# DRV8316.net
KiCad netlist of a schematic drawn in Altium Designer
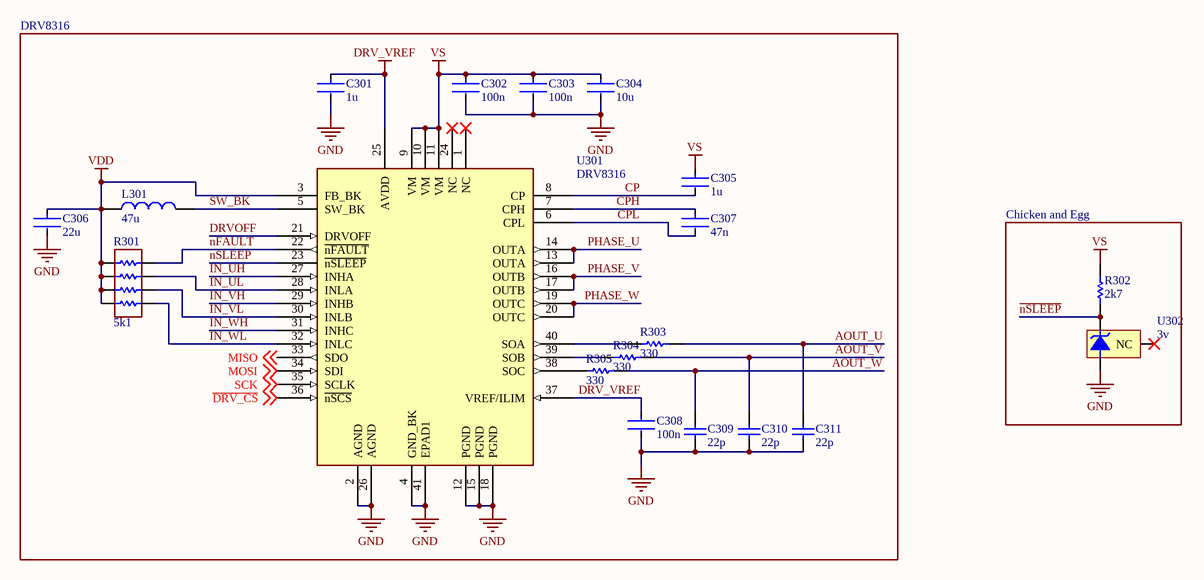
[diagram p0: DRV8316.SchDoc]

(export (version "E")
  (design (tool "Eeschema 10.0.6"))
  (components
    (comp (ref "C301")
      (value "1u")
      (footprint "FP-GRM155-0_1-MFG")
      (description "Chip Multilayer Ceramic Capacitors for General Purpose, 0402, 1.0uF, X5R, 15%, 20%, 50V")
      (libsource (lib "Main") (part "GRM155R61H105ME05D"))
    )
    (comp (ref "C302")
      (value "100n")
      (footprint "FP-GCM155-0_05-MFG")
      (description "Ceramic Capacitor for Automotive 100nF ±10% 50VDC X7R 0402 Paper T/R")
      (fields (field (name "TOLERANCE") "10%"))
      (libsource (lib "Main") (part "GCM155R71H104KE02J"))
    )
    (comp (ref "C303")
      (value "100n")
      (footprint "FP-GCM155-0_05-MFG")
      (description "Ceramic Capacitor for Automotive 100nF ±10% 50VDC X7R 0402 Paper T/R")
      (fields (field (name "TOLERANCE") "10%"))
      (libsource (lib "Main") (part "GCM155R71H104KE02J"))
    )
    (comp (ref "C304")
      (value "10u")
      (footprint "FP-GRT31C-0_2-IPC_C")
      (description "CAP CER 10UF 50V X5R 1206")
      (fields (field (name "TOLERANCE") "20%"))
      (libsource (lib "Main") (part "GRT31CR61H106ME01L"))
    )
    (comp (ref "C305")
      (value "1u")
      (footprint "FP-GRM155-0_1-MFG")
      (description "Chip Multilayer Ceramic Capacitors for General Purpose, 0402, 1.0uF, X5R, 15%, 20%, 50V")
      (libsource (lib "Main") (part "GRM155R61H105ME05D"))
    )
    (comp (ref "C306")
      (value "22u")
      (footprint "FP-GRM188-0_2-IPC_C")
      (description "Chip Multilayer Ceramic Capacitors for General Purpose, 0603, 22uF, X5R, 15%, 20%, 6.3V")
      (fields (field (name "TOLERANCE") "20%"))
      (libsource (lib "Main") (part "GRM188R60J226MEA0J"))
    )
    (comp (ref "C307")
      (value "47n")
      (footprint "FP-GRM155-0_05-MFG")
      (description "Chip Multilayer Ceramic Capacitors for General Purpose, 0402, 47000pF, X7R, 15%, 10%, 50V")
      (fields (field (name "TOLERANCE") "10%"))
      (libsource (lib "Main") (part "GRM155R71H473KE14D"))
    )
    (comp (ref "C308")
      (value "100n")
      (footprint "FP-GCM155-0_05-MFG")
      (description "Ceramic Capacitor for Automotive 100nF ±10% 50VDC X7R 0402 Paper T/R")
      (fields (field (name "TOLERANCE") "10%"))
      (libsource (lib "Main") (part "GCM155R71H104KE02J"))
    )
    (comp (ref "C309")
      (value "22p")
      (footprint "CAPC1005X55X25LL05T10")
      (fields (field (name "MANUFACTURER") "Murata") (field (name "PART NUMBER") "GRM1555C1H220GA01D"))
      (libsource (lib "Main") (part "GRM1555C1H220GA01D"))
    )
    (comp (ref "C310")
      (value "22p")
      (footprint "CAPC1005X55X25LL05T10")
      (fields (field (name "MANUFACTURER") "Murata") (field (name "PART NUMBER") "GRM1555C1H220GA01D"))
      (libsource (lib "Main") (part "GRM1555C1H220GA01D"))
    )
    (comp (ref "C311")
      (value "22p")
      (footprint "CAPC1005X55X25LL05T10")
      (fields (field (name "MANUFACTURER") "Murata") (field (name "PART NUMBER") "GRM1555C1H220GA01D"))
      (libsource (lib "Main") (part "GRM1555C1H220GA01D"))
    )
    (comp (ref "L301")
      (value "47u")
      (footprint "INDC3225X25N")
      (libsource (lib "Main") (part "L1210R470KDWIT"))
    )
    (comp (ref "R301")
      (value "5k1")
      (footprint "CAC-50P200X100-8L")
      (libsource (lib "Main") (part "EXB-28V512JX"))
    )
    (comp (ref "R302")
      (value "2k7")
      (footprint "RESC1005X04N")
      (fields (field (name "MANUFACTURER") "Panasonic") (field (name "PART NUMBER") "ERJ-2GEJ331X"))
      (libsource (lib "Main") (part "ERJ-2GEJ272X"))
    )
    (comp (ref "R303")
      (value "330")
      (footprint "RESC1005X04N")
      (fields (field (name "MANUFACTURER") "Panasonic") (field (name "PART NUMBER") "ERJ-2GEJ331X"))
      (libsource (lib "Main") (part "ERJ-2GEJ331X"))
    )
    (comp (ref "R304")
      (value "330")
      (footprint "RESC1005X04N")
      (fields (field (name "MANUFACTURER") "Panasonic") (field (name "PART NUMBER") "ERJ-2GEJ331X"))
      (libsource (lib "Main") (part "ERJ-2GEJ331X"))
    )
    (comp (ref "R305")
      (value "330")
      (footprint "RESC1005X04N")
      (fields (field (name "MANUFACTURER") "Panasonic") (field (name "PART NUMBER") "ERJ-2GEJ331X"))
      (libsource (lib "Main") (part "ERJ-2GEJ331X"))
    )
    (comp (ref "U301")
      (value "DRV8316")
      (footprint "QFN50P500X700X100_HS-41L")
      (libsource (lib "Main") (part "DRV8316"))
    )
    (comp (ref "U302")
      (value "3v")
      (footprint "SOT95P237X112-3L")
      (description "Precision Micropower Shunt Voltage Reference, 3-pin SOT-23, Pb-Free")
      (fields (field (name "MANUFACTURER") "National Semiconductor"))
      (libsource (lib "Main") (part "LM4040CIM3-3.0/NOPB"))
    )
  )
  (nets
    (net (code "1") (name "/AOUT_U") (class "Default")
      (node (ref "C311") (pin "2") (pinfunction "2_2") (pintype "passive"))
      (node (ref "R303") (pin "2") (pinfunction "2_2") (pintype "passive"))
    )
    (net (code "2") (name "/AOUT_V") (class "Default")
      (node (ref "C310") (pin "2") (pinfunction "2_2") (pintype "passive"))
      (node (ref "R304") (pin "2") (pinfunction "2_2") (pintype "passive"))
    )
    (net (code "3") (name "/AOUT_W") (class "Default")
      (node (ref "C309") (pin "2") (pinfunction "2_2") (pintype "passive"))
      (node (ref "R305") (pin "2") (pinfunction "2_2") (pintype "passive"))
    )
    (net (code "4") (name "/CP") (class "Default")
      (node (ref "C305") (pin "2") (pinfunction "2_2") (pintype "passive"))
      (node (ref "U301") (pin "8") (pinfunction "CP_8") (pintype "power_in"))
    )
    (net (code "5") (name "/CPH") (class "Default")
      (node (ref "C307") (pin "1") (pinfunction "1_1") (pintype "passive"))
      (node (ref "U301") (pin "7") (pinfunction "CPH_7") (pintype "power_in"))
    )
    (net (code "6") (name "/CPL") (class "Default")
      (node (ref "C307") (pin "2") (pinfunction "2_2") (pintype "passive"))
      (node (ref "U301") (pin "6") (pinfunction "CPL_6") (pintype "power_in"))
    )
    (net (code "7") (name "/DRVOFF") (class "Default")
      (node (ref "U301") (pin "21") (pinfunction "DRVOFF_21") (pintype "input"))
    )
    (net (code "8") (name "/IN_UH") (class "Default")
      (node (ref "U301") (pin "27") (pinfunction "INHA_27") (pintype "input"))
    )
    (net (code "9") (name "/IN_UL") (class "Default")
      (node (ref "R301") (pin "7") (pinfunction "7_7") (pintype "passive"))
      (node (ref "U301") (pin "28") (pinfunction "INLA_28") (pintype "input"))
    )
    (net (code "10") (name "/IN_VH") (class "Default")
      (node (ref "U301") (pin "29") (pinfunction "INHB_29") (pintype "input"))
    )
    (net (code "11") (name "/IN_VL") (class "Default")
      (node (ref "R301") (pin "6") (pinfunction "6_6") (pintype "passive"))
      (node (ref "U301") (pin "30") (pinfunction "INLB_30") (pintype "input"))
    )
    (net (code "12") (name "/IN_WH") (class "Default")
      (node (ref "U301") (pin "31") (pinfunction "INHC_31") (pintype "input"))
    )
    (net (code "13") (name "/IN_WL") (class "Default")
      (node (ref "R301") (pin "5") (pinfunction "5_5") (pintype "passive"))
      (node (ref "U301") (pin "32") (pinfunction "INLC_32") (pintype "input"))
    )
    (net (code "14") (name "/PHASE_U") (class "Default")
      (node (ref "U301") (pin "13") (pinfunction "OUTA_13") (pintype "output"))
      (node (ref "U301") (pin "14") (pinfunction "OUTA_14") (pintype "output"))
    )
    (net (code "15") (name "/PHASE_V") (class "Default")
      (node (ref "U301") (pin "16") (pinfunction "OUTB_16") (pintype "output"))
      (node (ref "U301") (pin "17") (pinfunction "OUTB_17") (pintype "output"))
    )
    (net (code "16") (name "/PHASE_W") (class "Default")
      (node (ref "U301") (pin "19") (pinfunction "OUTC_19") (pintype "output"))
      (node (ref "U301") (pin "20") (pinfunction "OUTC_20") (pintype "output"))
    )
    (net (code "17") (name "/SW_BK") (class "Default")
      (node (ref "L301") (pin "2") (pintype "passive"))
      (node (ref "U301") (pin "5") (pinfunction "SW_BK_5") (pintype "passive"))
    )
    (net (code "18") (name "/nFAULT") (class "Default")
      (node (ref "R301") (pin "8") (pinfunction "8_8") (pintype "passive"))
      (node (ref "U301") (pin "22") (pinfunction "nFAULT_22") (pintype "output"))
    )
    (net (code "19") (name "/nSLEEP") (class "Default")
      (node (ref "R302") (pin "1") (pinfunction "1_1") (pintype "passive"))
      (node (ref "U301") (pin "23") (pinfunction "nSLEEP_23") (pintype "passive"))
      (node (ref "U302") (pin "1") (pinfunction "+V_1") (pintype "passive"))
    )
    (net (code "20") (name "DRV_CS") (class "Default")
      (node (ref "U301") (pin "36") (pinfunction "nSCS_36") (pintype "input"))
    )
    (net (code "21") (name "DRV_VREF") (class "Default")
      (node (ref "C301") (pin "1") (pinfunction "1_1") (pintype "passive"))
      (node (ref "C308") (pin "1") (pinfunction "1_1") (pintype "passive"))
      (node (ref "U301") (pin "25") (pinfunction "AVDD_25") (pintype "power_in"))
      (node (ref "U301") (pin "37") (pinfunction "VREF/ILIM_37") (pintype "input"))
    )
    (net (code "22") (name "GND") (class "Default")
      (node (ref "C301") (pin "2") (pinfunction "2_2") (pintype "passive"))
      (node (ref "C302") (pin "2") (pinfunction "2_2") (pintype "passive"))
      (node (ref "C303") (pin "2") (pinfunction "2_2") (pintype "passive"))
      (node (ref "C304") (pin "2") (pinfunction "2_2") (pintype "passive"))
      (node (ref "C306") (pin "2") (pinfunction "2_2") (pintype "passive"))
      (node (ref "C308") (pin "2") (pinfunction "2_2") (pintype "passive"))
      (node (ref "C309") (pin "1") (pinfunction "1_1") (pintype "passive"))
      (node (ref "C310") (pin "1") (pinfunction "1_1") (pintype "passive"))
      (node (ref "C311") (pin "1") (pinfunction "1_1") (pintype "passive"))
      (node (ref "U301") (pin "12") (pinfunction "PGND_12") (pintype "power_in"))
      (node (ref "U301") (pin "15") (pinfunction "PGND_15") (pintype "power_in"))
      (node (ref "U301") (pin "18") (pinfunction "PGND_18") (pintype "power_in"))
      (node (ref "U301") (pin "2") (pinfunction "AGND_2") (pintype "power_in"))
      (node (ref "U301") (pin "26") (pinfunction "AGND_26") (pintype "power_in"))
      (node (ref "U301") (pin "4") (pinfunction "GND_BK_4") (pintype "power_in"))
      (node (ref "U301") (pin "41") (pinfunction "EPAD1_41") (pintype "power_in"))
      (node (ref "U302") (pin "2") (pinfunction "-V_2") (pintype "passive"))
    )
    (net (code "23") (name "MISO") (class "Default")
      (node (ref "U301") (pin "33") (pinfunction "SDO_33") (pintype "output"))
    )
    (net (code "24") (name "MOSI") (class "Default")
      (node (ref "U301") (pin "34") (pinfunction "SDI_34") (pintype "input"))
    )
    (net (code "25") (name "Net-(U301-SOA)") (class "Default")
      (node (ref "R303") (pin "1") (pinfunction "1_1") (pintype "passive"))
      (node (ref "U301") (pin "40") (pinfunction "SOA_40") (pintype "output"))
    )
    (net (code "26") (name "Net-(U301-SOB)") (class "Default")
      (node (ref "R304") (pin "1") (pinfunction "1_1") (pintype "passive"))
      (node (ref "U301") (pin "39") (pinfunction "SOB_39") (pintype "output"))
    )
    (net (code "27") (name "Net-(U301-SOC)") (class "Default")
      (node (ref "R305") (pin "1") (pinfunction "1_1") (pintype "passive"))
      (node (ref "U301") (pin "38") (pinfunction "SOC_38") (pintype "output"))
    )
    (net (code "28") (name "SCK") (class "Default")
      (node (ref "U301") (pin "35") (pinfunction "SCLK_35") (pintype "input"))
    )
    (net (code "29") (name "VDD") (class "Default")
      (node (ref "C306") (pin "1") (pinfunction "1_1") (pintype "passive"))
      (node (ref "L301") (pin "1") (pintype "passive"))
      (node (ref "R301") (pin "1") (pinfunction "1_1") (pintype "passive"))
      (node (ref "R301") (pin "2") (pinfunction "2_2") (pintype "passive"))
      (node (ref "R301") (pin "3") (pinfunction "3_3") (pintype "passive"))
      (node (ref "R301") (pin "4") (pinfunction "4_4") (pintype "passive"))
      (node (ref "U301") (pin "3") (pinfunction "FB_BK_3") (pintype "power_in"))
    )
    (net (code "30") (name "VS") (class "Default")
      (node (ref "C302") (pin "1") (pinfunction "1_1") (pintype "passive"))
      (node (ref "C303") (pin "1") (pinfunction "1_1") (pintype "passive"))
      (node (ref "C304") (pin "1") (pinfunction "1_1") (pintype "passive"))
      (node (ref "C305") (pin "1") (pinfunction "1_1") (pintype "passive"))
      (node (ref "R302") (pin "2") (pinfunction "2_2") (pintype "passive"))
      (node (ref "U301") (pin "10") (pinfunction "VM_10") (pintype "power_in"))
      (node (ref "U301") (pin "11") (pinfunction "VM_11") (pintype "power_in"))
      (node (ref "U301") (pin "9") (pinfunction "VM_9") (pintype "power_in"))
    )
    (net (code "31") (name "unconnected-(U301-NC-Pad1)") (class "Default")
      (node (ref "U301") (pin "1") (pinfunction "NC_1") (pintype "passive+no_connect"))
    )
    (net (code "32") (name "unconnected-(U301-NC-Pad24)") (class "Default")
      (node (ref "U301") (pin "24") (pinfunction "NC_24") (pintype "passive+no_connect"))
    )
    (net (code "33") (name "unconnected-(U302-NC-Pad3)") (class "Default")
      (node (ref "U302") (pin "3") (pinfunction "NC_3") (pintype "passive+no_connect"))
    )
  )
)
